# 03_-_Module_Sim.net
KiCad netlist of a schematic drawn in Altium Designer
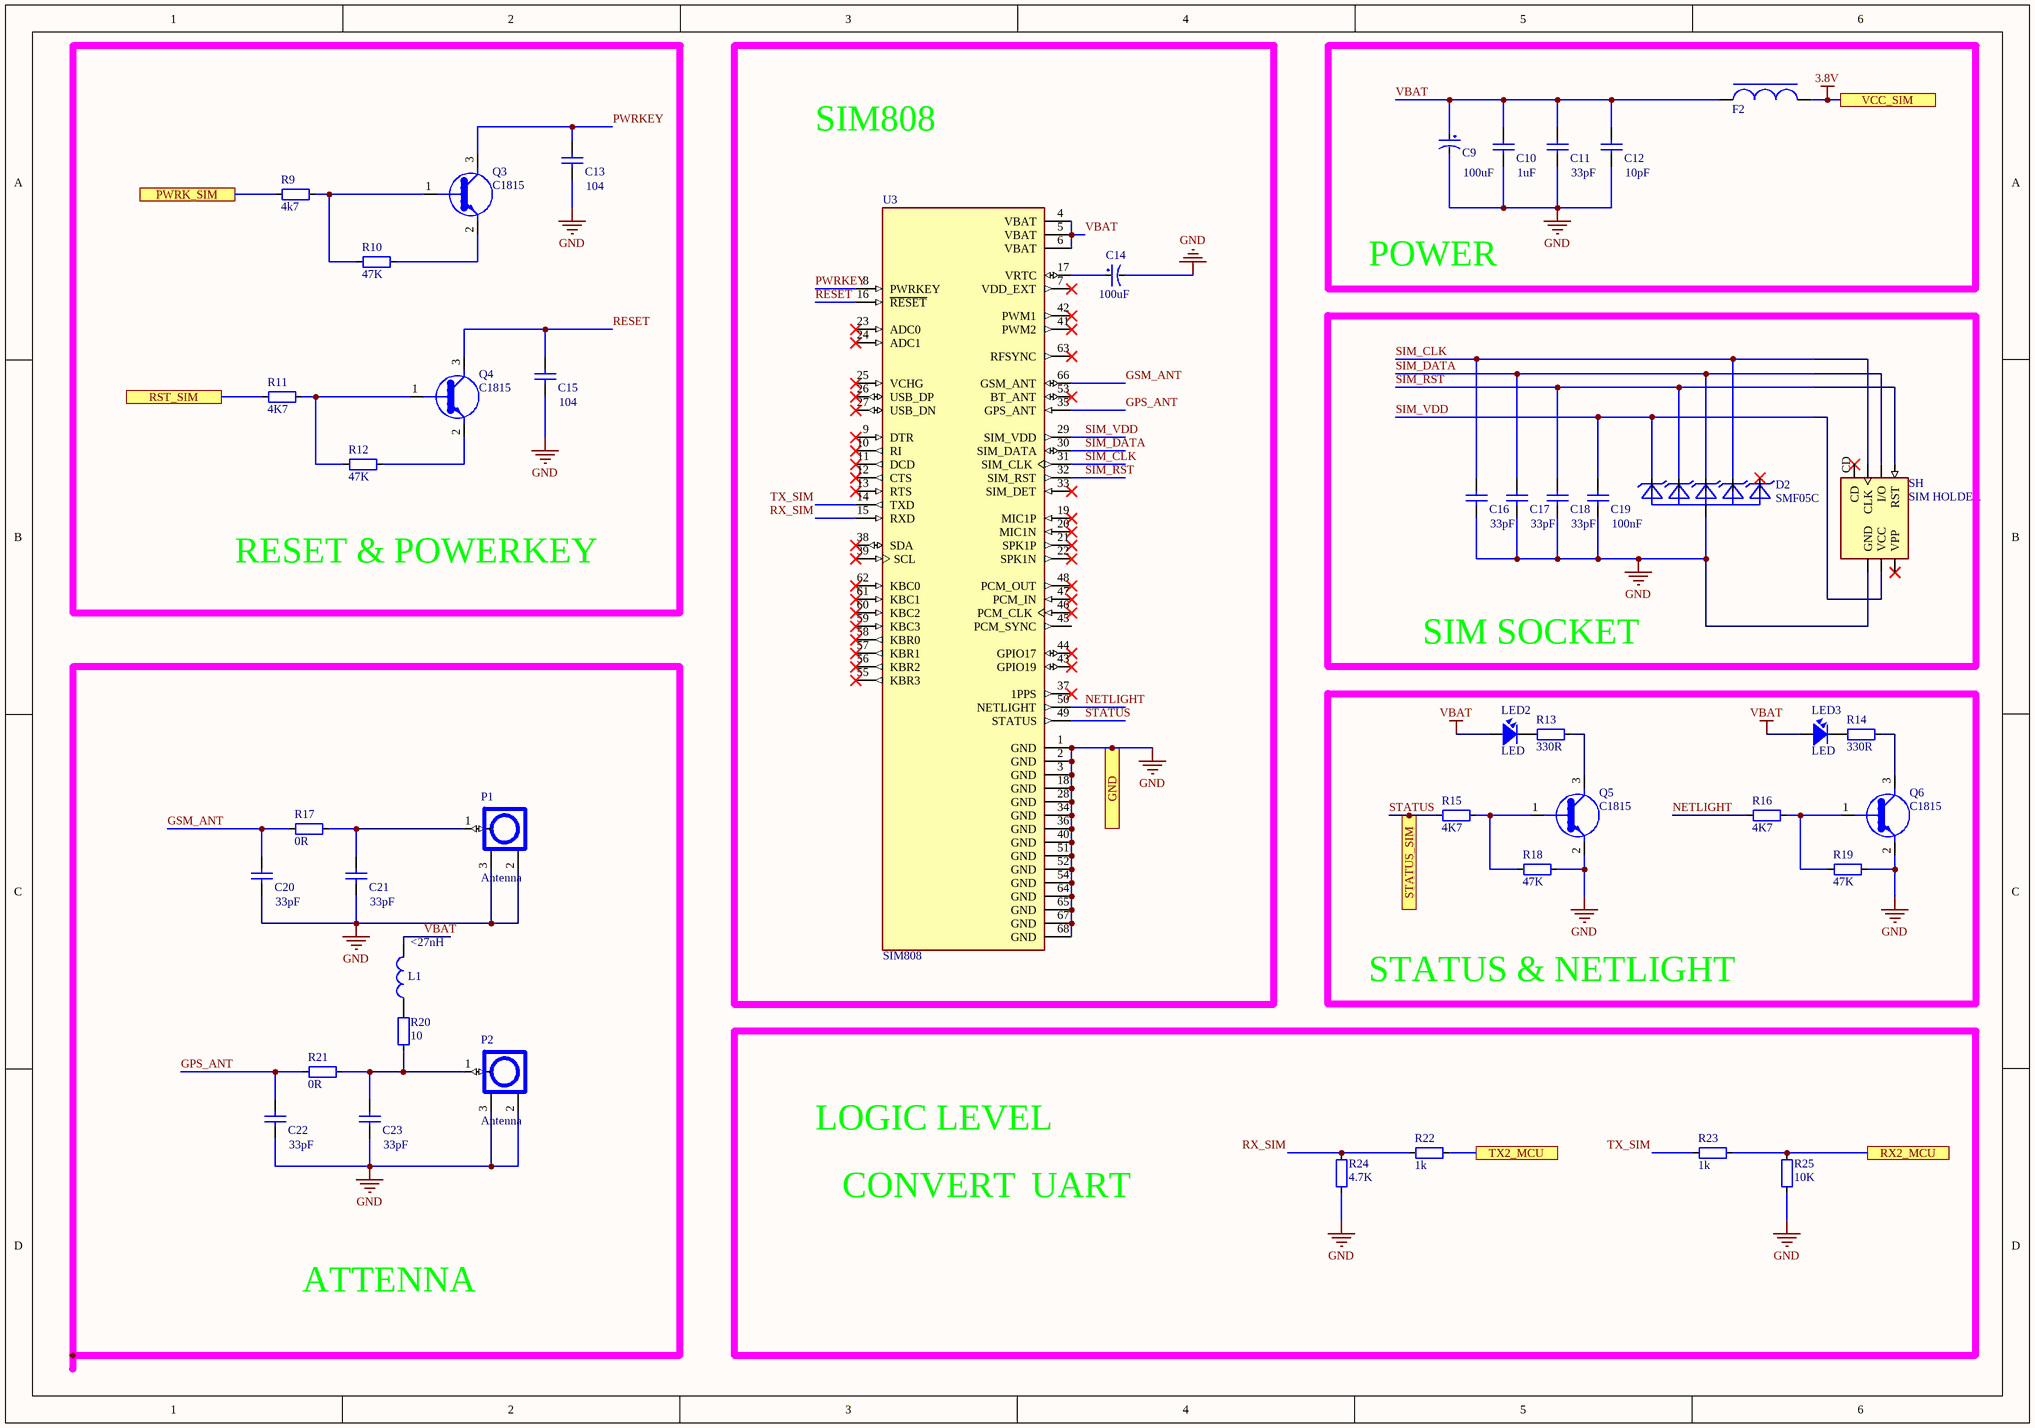
[diagram p0: [03] - Module Sim.SchDoc]

(export (version "E")
  (design (tool "Eeschema 10.0.6"))
  (components
    (comp (ref "C9")
      (value "100uF")
      (footprint "CAP-ALU-SMD-D")
      (description "Capacitor ALU SMD")
      (libsource (lib "HS_Lib") (part "Cap_ALU_Smd"))
    )
    (comp (ref "C10")
      (value "1uF")
      (footprint "CAP_0805")
      (description "Capacitor")
      (fields (field (name "PUBLISHER") "Altium Limited"))
      (libsource (lib "HS_Lib") (part "CapSMD"))
    )
    (comp (ref "C11")
      (value "33pF")
      (footprint "CAP_0805")
      (description "Capacitor")
      (fields (field (name "PUBLISHER") "Altium Limited"))
      (libsource (lib "HS_Lib") (part "CapSMD"))
    )
    (comp (ref "C12")
      (value "10pF")
      (footprint "CAP_0805")
      (description "Capacitor")
      (fields (field (name "PUBLISHER") "Altium Limited"))
      (libsource (lib "HS_Lib") (part "CapSMD"))
    )
    (comp (ref "C13")
      (value "104")
      (footprint "CAP_0805")
      (description "Capacitor")
      (fields (field (name "PUBLISHER") "Altium Limited"))
      (libsource (lib "HS_Lib") (part "CapSMD"))
    )
    (comp (ref "C14")
      (value "100uF")
      (footprint "CAP-ALU-SMD-D")
      (description "Capacitor ALU SMD")
      (libsource (lib "HS_Lib") (part "Cap_ALU_Smd"))
    )
    (comp (ref "C15")
      (value "104")
      (footprint "CAP_0805")
      (description "Capacitor")
      (fields (field (name "PUBLISHER") "Altium Limited"))
      (libsource (lib "HS_Lib") (part "CapSMD"))
    )
    (comp (ref "C16")
      (value "33pF")
      (footprint "CAP_0805")
      (description "Capacitor")
      (fields (field (name "PUBLISHER") "Altium Limited"))
      (libsource (lib "HS_Lib") (part "CapSMD"))
    )
    (comp (ref "C17")
      (value "33pF")
      (footprint "CAP_0805")
      (description "Capacitor")
      (fields (field (name "PUBLISHER") "Altium Limited"))
      (libsource (lib "HS_Lib") (part "CapSMD"))
    )
    (comp (ref "C18")
      (value "33pF")
      (footprint "CAP_0805")
      (description "Capacitor")
      (fields (field (name "PUBLISHER") "Altium Limited"))
      (libsource (lib "HS_Lib") (part "CapSMD"))
    )
    (comp (ref "C19")
      (value "100nF")
      (footprint "CAP_0805")
      (description "Capacitor")
      (fields (field (name "PUBLISHER") "Altium Limited"))
      (libsource (lib "HS_Lib") (part "CapSMD"))
    )
    (comp (ref "C20")
      (value "33pF")
      (footprint "CAP_0805")
      (description "Capacitor")
      (fields (field (name "PUBLISHER") "Altium Limited"))
      (libsource (lib "HS_Lib") (part "CapSMD"))
    )
    (comp (ref "C21")
      (value "33pF")
      (footprint "CAP_0805")
      (description "Capacitor")
      (fields (field (name "PUBLISHER") "Altium Limited"))
      (libsource (lib "HS_Lib") (part "CapSMD"))
    )
    (comp (ref "C22")
      (value "33pF")
      (footprint "CAP_0805")
      (description "Capacitor")
      (fields (field (name "PUBLISHER") "Altium Limited"))
      (libsource (lib "HS_Lib") (part "CapSMD"))
    )
    (comp (ref "C23")
      (value "33pF")
      (footprint "CAP_0805")
      (description "Capacitor")
      (fields (field (name "PUBLISHER") "Altium Limited"))
      (libsource (lib "HS_Lib") (part "CapSMD"))
    )
    (comp (ref "D2")
      (value "SMF05C")
      (footprint "SC70-6L")
      (description "12.5V Clamp 8A _8/20Âµs_ Ipp Tvs Diode Surface Mount SC-88/SC70-6/SOT-363")
      (fields (field (name "MF") "ON Semiconductor") (field (name "MANUFACTURER") "Semtech"))
      (libsource (lib "HS_Lib") (part "SMF05C"))
    )
    (comp (ref "F2")
      (value "Ferrite Bead")
      (footprint "Ferrite_0805")
      (fields
        (field (name "MANUFACTURER") "Murata")
        (field (name "MANUFACTURER PART NUMBER") "BLM21PG300SN1D")
        (field (name "TOLERANCE") "25%")
      )
      (libsource (lib "HS_Lib") (part "Ferrite Bead"))
    )
    (comp (ref "L1")
      (value "<27nH")
      (footprint "RTK_Rover_Lib:L-SMD-D-7.3x7.3")
      (libsource (lib "HS_Lib") (part "Inductor"))
    )
    (comp (ref "LED2")
      (value "LED")
      (footprint "LED-0805-Red")
      (description "LED Single colour Green and Red")
      (libsource (lib "RTK_Rover_Lib") (part "LED"))
    )
    (comp (ref "LED3")
      (value "LED")
      (footprint "LED-0805-Red")
      (description "LED Single colour Green and Red")
      (libsource (lib "RTK_Rover_Lib") (part "LED"))
    )
    (comp (ref "P1")
      (value "Antenna")
      (footprint "IPXS")
      (description "Antenna GSM GPS")
      (libsource (lib "HS_Lib") (part "IPXSx66"))
    )
    (comp (ref "P2")
      (value "Antenna")
      (footprint "IPXS")
      (description "Antenna GSM GPS")
      (libsource (lib "HS_Lib") (part "IPXSx66"))
    )
    (comp (ref "Q3")
      (value "C1815")
      (footprint "SOT23")
      (description "Bipolar _BJT_ Transistor NPN 25V 1.5A 100MHz 300mW Surface Mount SOT-23")
      (fields (field (name "MF") "Comchip Technology") (field (name "MP") "SS8050-G"))
      (libsource (lib "HS_Lib") (part "C1815"))
    )
    (comp (ref "Q4")
      (value "C1815")
      (footprint "SOT23")
      (description "Bipolar _BJT_ Transistor NPN 25V 1.5A 100MHz 300mW Surface Mount SOT-23")
      (fields (field (name "MF") "Comchip Technology") (field (name "MP") "SS8050-G"))
      (libsource (lib "HS_Lib") (part "C1815"))
    )
    (comp (ref "Q5")
      (value "C1815")
      (footprint "SOT23")
      (description "Bipolar _BJT_ Transistor NPN 25V 1.5A 100MHz 300mW Surface Mount SOT-23")
      (fields (field (name "MF") "Comchip Technology") (field (name "MP") "SS8050-G"))
      (libsource (lib "HS_Lib") (part "C1815"))
    )
    (comp (ref "Q6")
      (value "C1815")
      (footprint "SOT23")
      (description "Bipolar _BJT_ Transistor NPN 25V 1.5A 100MHz 300mW Surface Mount SOT-23")
      (fields (field (name "MF") "Comchip Technology") (field (name "MP") "SS8050-G"))
      (libsource (lib "HS_Lib") (part "C1815"))
    )
    (comp (ref "R9")
      (value "4k7")
      (footprint "RES-SMD-0805")
      (description "Resistor")
      (fields
        (field (name "MANUFACTURER") "Generic Components")
        (field (name "PUBLISHER") "Altium Hobart Technology Centre")
      )
      (libsource (lib "HS_Lib") (part "Resistor - SMD"))
    )
    (comp (ref "R10")
      (value "47K")
      (footprint "RES-SMD-0805")
      (description "Resistor")
      (fields
        (field (name "MANUFACTURER") "Generic Components")
        (field (name "PUBLISHER") "Altium Hobart Technology Centre")
      )
      (libsource (lib "HS_Lib") (part "Resistor - SMD"))
    )
    (comp (ref "R11")
      (value "4K7")
      (footprint "RES-SMD-0805")
      (description "Resistor")
      (fields
        (field (name "MANUFACTURER") "Generic Components")
        (field (name "PUBLISHER") "Altium Hobart Technology Centre")
      )
      (libsource (lib "HS_Lib") (part "Resistor - SMD"))
    )
    (comp (ref "R12")
      (value "47K")
      (footprint "RES-SMD-0805")
      (description "Resistor")
      (fields
        (field (name "MANUFACTURER") "Generic Components")
        (field (name "PUBLISHER") "Altium Hobart Technology Centre")
      )
      (libsource (lib "HS_Lib") (part "Resistor - SMD"))
    )
    (comp (ref "R13")
      (value "330R")
      (footprint "RES-SMD-0805")
      (description "Resistor")
      (fields
        (field (name "MANUFACTURER") "Generic Components")
        (field (name "PUBLISHER") "Altium Hobart Technology Centre")
      )
      (libsource (lib "RTK_Rover_Lib") (part "Resistor - SMD"))
    )
    (comp (ref "R14")
      (value "330R")
      (footprint "RES-SMD-0805")
      (description "Resistor")
      (fields
        (field (name "MANUFACTURER") "Generic Components")
        (field (name "PUBLISHER") "Altium Hobart Technology Centre")
      )
      (libsource (lib "RTK_Rover_Lib") (part "Resistor - SMD"))
    )
    (comp (ref "R15")
      (value "4K7")
      (footprint "RES-SMD-0805")
      (description "Resistor")
      (fields
        (field (name "MANUFACTURER") "Generic Components")
        (field (name "PUBLISHER") "Altium Hobart Technology Centre")
      )
      (libsource (lib "RTK_Rover_Lib") (part "Resistor - SMD"))
    )
    (comp (ref "R16")
      (value "4K7")
      (footprint "RES-SMD-0805")
      (description "Resistor")
      (fields
        (field (name "MANUFACTURER") "Generic Components")
        (field (name "PUBLISHER") "Altium Hobart Technology Centre")
      )
      (libsource (lib "RTK_Rover_Lib") (part "Resistor - SMD"))
    )
    (comp (ref "R17")
      (value "0R")
      (footprint "RES-SMD-0603")
      (description "Resistor")
      (fields
        (field (name "MANUFACTURER") "Generic Components")
        (field (name "PUBLISHER") "Altium Hobart Technology Centre")
      )
      (libsource (lib "My Library") (part "Resistor - SMD"))
    )
    (comp (ref "R18")
      (value "47K")
      (footprint "RES-SMD-0805")
      (description "Resistor")
      (fields
        (field (name "MANUFACTURER") "Generic Components")
        (field (name "PUBLISHER") "Altium Hobart Technology Centre")
      )
      (libsource (lib "RTK_Rover_Lib") (part "Resistor - SMD"))
    )
    (comp (ref "R19")
      (value "47K")
      (footprint "RES-SMD-0805")
      (description "Resistor")
      (fields
        (field (name "MANUFACTURER") "Generic Components")
        (field (name "PUBLISHER") "Altium Hobart Technology Centre")
      )
      (libsource (lib "RTK_Rover_Lib") (part "Resistor - SMD"))
    )
    (comp (ref "R20")
      (value "10")
      (footprint "RES-SMD-0603")
      (description "Resistor")
      (fields
        (field (name "MANUFACTURER") "Generic Components")
        (field (name "PUBLISHER") "Altium Hobart Technology Centre")
      )
      (libsource (lib "HS_Lib") (part "Resistor - SMD"))
    )
    (comp (ref "R21")
      (value "0R")
      (footprint "RES-SMD-0603")
      (description "Resistor")
      (fields
        (field (name "MANUFACTURER") "Generic Components")
        (field (name "PUBLISHER") "Altium Hobart Technology Centre")
      )
      (libsource (lib "My Library") (part "Resistor - SMD"))
    )
    (comp (ref "R22")
      (value "1k")
      (footprint "RES-SMD-0805")
      (description "Resistor")
      (fields
        (field (name "MANUFACTURER") "Generic Components")
        (field (name "PUBLISHER") "Altium Hobart Technology Centre")
      )
      (libsource (lib "HS_Lib") (part "Resistor - SMD"))
    )
    (comp (ref "R23")
      (value "1k")
      (footprint "RES-SMD-0805")
      (description "Resistor")
      (fields
        (field (name "MANUFACTURER") "Generic Components")
        (field (name "PUBLISHER") "Altium Hobart Technology Centre")
      )
      (libsource (lib "HS_Lib") (part "Resistor - SMD"))
    )
    (comp (ref "R24")
      (value "4.7K")
      (footprint "RES-SMD-0805")
      (description "Resistor")
      (fields
        (field (name "MANUFACTURER") "Generic Components")
        (field (name "PUBLISHER") "Altium Hobart Technology Centre")
      )
      (libsource (lib "HS_Lib") (part "Resistor - SMD"))
    )
    (comp (ref "R25")
      (value "10K")
      (footprint "RES-SMD-0805")
      (description "Resistor")
      (fields
        (field (name "MANUFACTURER") "Generic Components")
        (field (name "PUBLISHER") "Altium Hobart Technology Centre")
      )
      (libsource (lib "HS_Lib") (part "Resistor - SMD"))
    )
    (comp (ref "SH")
      (value "SIM HOLDER")
      (footprint "GCT_SIM7100-6-1-15-00-A_REVC")
      (description "7 _6 + 1_ Position Card Connector Micro SIM Surface Mount, Right Angle Gold")
      (fields (field (name "MP") "SIM7100-6-1-15-00-A") (field (name "MF") "Global Connector Technology"))
      (libsource (lib "HS_Lib") (part "SIM HOLDER"))
    )
    (comp (ref "U3")
      (value "SIM808")
      (footprint "XCVR_SIM808")
      (description "SIM808 GPS, GPRS/GSM RF Arduino Platform Evaluation Expansion Board")
      (fields (field (name "MF") "Adafruit Industries"))
      (libsource (lib "HS_Lib") (part "SIM808"))
    )
  )
  (nets
    (net (code "1") (name "/GPS_ANT") (class "Default")
      (node (ref "C22") (pin "2") (pinfunction "2_2") (pintype "passive"))
      (node (ref "R21") (pin "1") (pinfunction "1_1") (pintype "passive"))
      (node (ref "U3") (pin "35") (pinfunction "GPS_ANT_35") (pintype "input"))
    )
    (net (code "2") (name "/GSM_ANT") (class "Default")
      (node (ref "C20") (pin "2") (pinfunction "2_2") (pintype "passive"))
      (node (ref "R17") (pin "1") (pinfunction "1_1") (pintype "passive"))
      (node (ref "U3") (pin "66") (pinfunction "GSM_ANT_66") (pintype "bidirectional"))
    )
    (net (code "3") (name "/NETLIGHT") (class "Default")
      (node (ref "R16") (pin "1") (pinfunction "1_1") (pintype "passive"))
      (node (ref "U3") (pin "50") (pinfunction "NETLIGHT_50") (pintype "output"))
    )
    (net (code "4") (name "/PWRKEY") (class "Default")
      (node (ref "C13") (pin "2") (pinfunction "2_2") (pintype "passive"))
      (node (ref "Q3") (pin "3") (pinfunction "C_3") (pintype "power_in"))
      (node (ref "U3") (pin "8") (pinfunction "PWRKEY_8") (pintype "input"))
    )
    (net (code "5") (name "/PWRK_SIM") (class "Default")
      (node (ref "R9") (pin "1") (pinfunction "1_1") (pintype "passive"))
    )
    (net (code "6") (name "/RESET") (class "Default")
      (node (ref "C15") (pin "2") (pinfunction "2_2") (pintype "passive"))
      (node (ref "Q4") (pin "3") (pinfunction "C_3") (pintype "power_in"))
      (node (ref "U3") (pin "16") (pinfunction "~{RESET}_16") (pintype "input"))
    )
    (net (code "7") (name "/RST_SIM") (class "Default")
      (node (ref "R11") (pin "1") (pinfunction "1_1") (pintype "passive"))
    )
    (net (code "8") (name "/RX2_MCU") (class "Default")
      (node (ref "R23") (pin "1") (pinfunction "1_1") (pintype "passive"))
      (node (ref "R25") (pin "1") (pinfunction "1_1") (pintype "passive"))
    )
    (net (code "9") (name "/RX_SIM") (class "Default")
      (node (ref "R22") (pin "2") (pinfunction "2_2") (pintype "passive"))
      (node (ref "R24") (pin "2") (pinfunction "2_2") (pintype "passive"))
      (node (ref "U3") (pin "15") (pinfunction "RXD_15") (pintype "input"))
    )
    (net (code "10") (name "/SIM_CLK") (class "Default")
      (node (ref "C16") (pin "2") (pinfunction "2_2") (pintype "passive"))
      (node (ref "D2") (pin "5") (pinfunction "C4_5") (pintype "passive"))
      (node (ref "SH") (pin "C3") (pinfunction "CLK_C3") (pintype "bidirectional"))
      (node (ref "U3") (pin "31") (pinfunction "SIM_CLK_31") (pintype "output"))
    )
    (net (code "11") (name "/SIM_DATA") (class "Default")
      (node (ref "C17") (pin "2") (pinfunction "2_2") (pintype "passive"))
      (node (ref "D2") (pin "4") (pinfunction "C3_4") (pintype "passive"))
      (node (ref "SH") (pin "C7") (pinfunction "I/O_C7") (pintype "bidirectional"))
      (node (ref "U3") (pin "30") (pinfunction "SIM_DATA_30") (pintype "bidirectional"))
    )
    (net (code "12") (name "/SIM_RST") (class "Default")
      (node (ref "C18") (pin "2") (pinfunction "2_2") (pintype "passive"))
      (node (ref "D2") (pin "3") (pinfunction "C2_3") (pintype "passive"))
      (node (ref "SH") (pin "C2") (pinfunction "RST_C2") (pintype "input"))
      (node (ref "U3") (pin "32") (pinfunction "SIM_RST_32") (pintype "output"))
    )
    (net (code "13") (name "/SIM_VDD") (class "Default")
      (node (ref "C19") (pin "2") (pinfunction "2_2") (pintype "passive"))
      (node (ref "D2") (pin "1") (pinfunction "C1_1") (pintype "passive"))
      (node (ref "SH") (pin "C1") (pinfunction "VCC_C1") (pintype "power_in"))
      (node (ref "U3") (pin "29") (pinfunction "SIM_VDD_29") (pintype "output"))
    )
    (net (code "14") (name "/STATUS") (class "Default")
      (node (ref "R15") (pin "2") (pinfunction "2_2") (pintype "passive"))
      (node (ref "U3") (pin "49") (pinfunction "STATUS_49") (pintype "output"))
    )
    (net (code "15") (name "/TX2_MCU") (class "Default")
      (node (ref "R22") (pin "1") (pinfunction "1_1") (pintype "passive"))
    )
    (net (code "16") (name "/TX_SIM") (class "Default")
      (node (ref "R23") (pin "2") (pinfunction "2_2") (pintype "passive"))
      (node (ref "U3") (pin "14") (pinfunction "TXD_14") (pintype "output"))
    )
    (net (code "17") (name "3.8V") (class "Default")
      (node (ref "F2") (pin "2") (pinfunction "2_2") (pintype "power_in"))
    )
    (net (code "18") (name "GND") (class "Default")
      (node (ref "C10") (pin "1") (pinfunction "1_1") (pintype "passive"))
      (node (ref "C11") (pin "1") (pinfunction "1_1") (pintype "passive"))
      (node (ref "C12") (pin "1") (pinfunction "1_1") (pintype "passive"))
      (node (ref "C13") (pin "1") (pinfunction "1_1") (pintype "passive"))
      (node (ref "C14") (pin "2") (pinfunction "2_2") (pintype "passive"))
      (node (ref "C15") (pin "1") (pinfunction "1_1") (pintype "passive"))
      (node (ref "C16") (pin "1") (pinfunction "1_1") (pintype "passive"))
      (node (ref "C17") (pin "1") (pinfunction "1_1") (pintype "passive"))
      (node (ref "C18") (pin "1") (pinfunction "1_1") (pintype "passive"))
      (node (ref "C19") (pin "1") (pinfunction "1_1") (pintype "passive"))
      (node (ref "C20") (pin "1") (pinfunction "1_1") (pintype "passive"))
      (node (ref "C21") (pin "1") (pinfunction "1_1") (pintype "passive"))
      (node (ref "C22") (pin "1") (pinfunction "1_1") (pintype "passive"))
      (node (ref "C23") (pin "1") (pinfunction "1_1") (pintype "passive"))
      (node (ref "C9") (pin "2") (pinfunction "2_2") (pintype "passive"))
      (node (ref "D2") (pin "2") (pinfunction "A_2") (pintype "passive"))
      (node (ref "P1") (pin "2") (pintype "passive"))
      (node (ref "P1") (pin "3") (pintype "passive"))
      (node (ref "P2") (pin "2") (pintype "passive"))
      (node (ref "P2") (pin "3") (pintype "passive"))
      (node (ref "Q5") (pin "2") (pinfunction "E_2") (pintype "power_in"))
      (node (ref "Q6") (pin "2") (pinfunction "E_2") (pintype "power_in"))
      (node (ref "R18") (pin "2") (pinfunction "2_2") (pintype "passive"))
      (node (ref "R19") (pin "2") (pinfunction "2_2") (pintype "passive"))
      (node (ref "R24") (pin "1") (pinfunction "1_1") (pintype "passive"))
      (node (ref "R25") (pin "2") (pinfunction "2_2") (pintype "passive"))
      (node (ref "SH") (pin "C5") (pinfunction "GND_C5") (pintype "power_in"))
      (node (ref "U3") (pin "1") (pinfunction "GND_1") (pintype "power_in"))
      (node (ref "U3") (pin "18") (pinfunction "GND_18") (pintype "power_in"))
      (node (ref "U3") (pin "2") (pinfunction "GND_2") (pintype "power_in"))
      (node (ref "U3") (pin "28") (pinfunction "GND_28") (pintype "power_in"))
      (node (ref "U3") (pin "3") (pinfunction "GND_3") (pintype "power_in"))
      (node (ref "U3") (pin "34") (pinfunction "GND_34") (pintype "power_in"))
      (node (ref "U3") (pin "36") (pinfunction "GND_36") (pintype "power_in"))
      (node (ref "U3") (pin "40") (pinfunction "GND_40") (pintype "power_in"))
      (node (ref "U3") (pin "51") (pinfunction "GND_51") (pintype "power_in"))
      (node (ref "U3") (pin "52") (pinfunction "GND_52") (pintype "power_in"))
      (node (ref "U3") (pin "54") (pinfunction "GND_54") (pintype "power_in"))
      (node (ref "U3") (pin "64") (pinfunction "GND_64") (pintype "power_in"))
      (node (ref "U3") (pin "65") (pinfunction "GND_65") (pintype "power_in"))
      (node (ref "U3") (pin "67") (pinfunction "GND_67") (pintype "power_in"))
      (node (ref "U3") (pin "68") (pinfunction "GND_68") (pintype "power_in"))
    )
    (net (code "19") (name "Net-(C21-Pad2)") (class "Default")
      (node (ref "C21") (pin "2") (pinfunction "2_2") (pintype "passive"))
      (node (ref "P1") (pin "1") (pintype "bidirectional"))
      (node (ref "R17") (pin "2") (pinfunction "2_2") (pintype "passive"))
    )
    (net (code "20") (name "Net-(C23-Pad2)") (class "Default")
      (node (ref "C23") (pin "2") (pinfunction "2_2") (pintype "passive"))
      (node (ref "P2") (pin "1") (pintype "bidirectional"))
      (node (ref "R20") (pin "1") (pinfunction "1_1") (pintype "passive"))
      (node (ref "R21") (pin "2") (pinfunction "2_2") (pintype "passive"))
    )
    (net (code "21") (name "Net-(L1-Pad1)") (class "Default")
      (node (ref "L1") (pin "1") (pinfunction "1_1") (pintype "passive"))
      (node (ref "R20") (pin "2") (pinfunction "2_2") (pintype "passive"))
    )
    (net (code "22") (name "Net-(LED2-Pad2)") (class "Default")
      (node (ref "LED2") (pin "2") (pinfunction "2_2") (pintype "passive"))
      (node (ref "R13") (pin "1") (pinfunction "1_1") (pintype "passive"))
    )
    (net (code "23") (name "Net-(LED3-Pad2)") (class "Default")
      (node (ref "LED3") (pin "2") (pinfunction "2_2") (pintype "passive"))
      (node (ref "R14") (pin "1") (pinfunction "1_1") (pintype "passive"))
    )
    (net (code "24") (name "Net-(Q3-B)") (class "Default")
      (node (ref "Q3") (pin "1") (pinfunction "B_1") (pintype "power_in"))
      (node (ref "R10") (pin "1") (pinfunction "1_1") (pintype "passive"))
      (node (ref "R9") (pin "2") (pinfunction "2_2") (pintype "passive"))
    )
    (net (code "25") (name "Net-(Q3-E)") (class "Default")
      (node (ref "Q3") (pin "2") (pinfunction "E_2") (pintype "power_in"))
      (node (ref "R10") (pin "2") (pinfunction "2_2") (pintype "passive"))
    )
    (net (code "26") (name "Net-(Q4-B)") (class "Default")
      (node (ref "Q4") (pin "1") (pinfunction "B_1") (pintype "power_in"))
      (node (ref "R11") (pin "2") (pinfunction "2_2") (pintype "passive"))
      (node (ref "R12") (pin "1") (pinfunction "1_1") (pintype "passive"))
    )
    (net (code "27") (name "Net-(Q4-E)") (class "Default")
      (node (ref "Q4") (pin "2") (pinfunction "E_2") (pintype "power_in"))
      (node (ref "R12") (pin "2") (pinfunction "2_2") (pintype "passive"))
    )
    (net (code "28") (name "Net-(Q5-B)") (class "Default")
      (node (ref "Q5") (pin "1") (pinfunction "B_1") (pintype "power_in"))
      (node (ref "R15") (pin "1") (pinfunction "1_1") (pintype "passive"))
      (node (ref "R18") (pin "1") (pinfunction "1_1") (pintype "passive"))
    )
    (net (code "29") (name "Net-(Q5-C)") (class "Default")
      (node (ref "Q5") (pin "3") (pinfunction "C_3") (pintype "power_in"))
      (node (ref "R13") (pin "2") (pinfunction "2_2") (pintype "passive"))
    )
    (net (code "30") (name "Net-(Q6-B)") (class "Default")
      (node (ref "Q6") (pin "1") (pinfunction "B_1") (pintype "power_in"))
      (node (ref "R16") (pin "2") (pinfunction "2_2") (pintype "passive"))
      (node (ref "R19") (pin "1") (pinfunction "1_1") (pintype "passive"))
    )
    (net (code "31") (name "Net-(Q6-C)") (class "Default")
      (node (ref "Q6") (pin "3") (pinfunction "C_3") (pintype "power_in"))
      (node (ref "R14") (pin "2") (pinfunction "2_2") (pintype "passive"))
    )
    (net (code "32") (name "Net-(U3-VRTC)") (class "Default")
      (node (ref "C14") (pin "1") (pinfunction "1_1") (pintype "passive"))
      (node (ref "U3") (pin "17") (pinfunction "VRTC_17") (pintype "bidirectional"))
    )
    (net (code "33") (name "VBAT") (class "Default")
      (node (ref "C10") (pin "2") (pinfunction "2_2") (pintype "passive"))
      (node (ref "C11") (pin "2") (pinfunction "2_2") (pintype "passive"))
      (node (ref "C12") (pin "2") (pinfunction "2_2") (pintype "passive"))
      (node (ref "C9") (pin "1") (pinfunction "1_1") (pintype "passive"))
      (node (ref "F2") (pin "1") (pinfunction "1_1") (pintype "power_in"))
      (node (ref "L1") (pin "2") (pinfunction "2_2") (pintype "passive"))
      (node (ref "LED2") (pin "1") (pinfunction "1_1") (pintype "passive"))
      (node (ref "LED3") (pin "1") (pinfunction "1_1") (pintype "passive"))
      (node (ref "U3") (pin "4") (pinfunction "VBAT_4") (pintype "power_in"))
      (node (ref "U3") (pin "5") (pinfunction "VBAT_5") (pintype "power_in"))
      (node (ref "U3") (pin "6") (pinfunction "VBAT_6") (pintype "power_in"))
    )
    (net (code "34") (name "unconnected-(D2-C5-Pad6)") (class "Default")
      (node (ref "D2") (pin "6") (pinfunction "C5_6") (pintype "passive+no_connect"))
    )
    (net (code "35") (name "unconnected-(SH-PadCD)") (class "Default")
      (node (ref "SH") (pin "CD") (pinfunction "CD_CD") (pintype "passive+no_connect"))
    )
    (net (code "36") (name "unconnected-(SH-VPP-PadC6)") (class "Default")
      (node (ref "SH") (pin "C6") (pinfunction "VPP_C6") (pintype "power_in+no_connect"))
    )
    (net (code "37") (name "unconnected-(U3-1PPS-Pad37)") (class "Default")
      (node (ref "U3") (pin "37") (pinfunction "1PPS_37") (pintype "output+no_connect"))
    )
    (net (code "38") (name "unconnected-(U3-ADC0-Pad23)") (class "Default")
      (node (ref "U3") (pin "23") (pinfunction "ADC0_23") (pintype "input+no_connect"))
    )
    (net (code "39") (name "unconnected-(U3-ADC1-Pad24)") (class "Default")
      (node (ref "U3") (pin "24") (pinfunction "ADC1_24") (pintype "input+no_connect"))
    )
    (net (code "40") (name "unconnected-(U3-BT_ANT-Pad53)") (class "Default")
      (node (ref "U3") (pin "53") (pinfunction "BT_ANT_53") (pintype "bidirectional+no_connect"))
    )
    (net (code "41") (name "unconnected-(U3-CTS-Pad12)") (class "Default")
      (node (ref "U3") (pin "12") (pinfunction "CTS_12") (pintype "output+no_connect"))
    )
    (net (code "42") (name "unconnected-(U3-DCD-Pad11)") (class "Default")
      (node (ref "U3") (pin "11") (pinfunction "DCD_11") (pintype "output+no_connect"))
    )
    (net (code "43") (name "unconnected-(U3-DTR-Pad9)") (class "Default")
      (node (ref "U3") (pin "9") (pinfunction "DTR_9") (pintype "input+no_connect"))
    )
    (net (code "44") (name "unconnected-(U3-GPIO17-Pad44)") (class "Default")
      (node (ref "U3") (pin "44") (pinfunction "GPIO17_44") (pintype "bidirectional+no_connect"))
    )
    (net (code "45") (name "unconnected-(U3-GPIO19-Pad43)") (class "Default")
      (node (ref "U3") (pin "43") (pinfunction "GPIO19_43") (pintype "bidirectional+no_connect"))
    )
    (net (code "46") (name "unconnected-(U3-KBC0-Pad62)") (class "Default")
      (node (ref "U3") (pin "62") (pinfunction "KBC0_62") (pintype "input+no_connect"))
    )
    (net (code "47") (name "unconnected-(U3-KBC1-Pad61)") (class "Default")
      (node (ref "U3") (pin "61") (pinfunction "KBC1_61") (pintype "input+no_connect"))
    )
    (net (code "48") (name "unconnected-(U3-KBC2-Pad60)") (class "Default")
      (node (ref "U3") (pin "60") (pinfunction "KBC2_60") (pintype "input+no_connect"))
    )
    (net (code "49") (name "unconnected-(U3-KBC3-Pad59)") (class "Default")
      (node (ref "U3") (pin "59") (pinfunction "KBC3_59") (pintype "input+no_connect"))
    )
    (net (code "50") (name "unconnected-(U3-KBR0-Pad58)") (class "Default")
      (node (ref "U3") (pin "58") (pinfunction "KBR0_58") (pintype "output+no_connect"))
    )
    (net (code "51") (name "unconnected-(U3-KBR1-Pad57)") (class "Default")
      (node (ref "U3") (pin "57") (pinfunction "KBR1_57") (pintype "output+no_connect"))
    )
    (net (code "52") (name "unconnected-(U3-KBR2-Pad56)") (class "Default")
      (node (ref "U3") (pin "56") (pinfunction "KBR2_56") (pintype "output+no_connect"))
    )
    (net (code "53") (name "unconnected-(U3-KBR3-Pad55)") (class "Default")
      (node (ref "U3") (pin "55") (pinfunction "KBR3_55") (pintype "output+no_connect"))
    )
    (net (code "54") (name "unconnected-(U3-MIC1N-Pad20)") (class "Default")
      (node (ref "U3") (pin "20") (pinfunction "MIC1N_20") (pintype "input+no_connect"))
    )
    (net (code "55") (name "unconnected-(U3-MIC1P-Pad19)") (class "Default")
      (node (ref "U3") (pin "19") (pinfunction "MIC1P_19") (pintype "input+no_connect"))
    )
    (net (code "56") (name "unconnected-(U3-PCM_CLK-Pad46)") (class "Default")
      (node (ref "U3") (pin "46") (pinfunction "PCM_CLK_46") (pintype "input+no_connect"))
    )
    (net (code "57") (name "unconnected-(U3-PCM_IN-Pad47)") (class "Default")
      (node (ref "U3") (pin "47") (pinfunction "PCM_IN_47") (pintype "input+no_connect"))
    )
    (net (code "58") (name "unconnected-(U3-PCM_OUT-Pad48)") (class "Default")
      (node (ref "U3") (pin "48") (pinfunction "PCM_OUT_48") (pintype "output+no_connect"))
    )
    (net (code "59") (name "unconnected-(U3-PCM_SYNC-Pad45)") (class "Default")
      (node (ref "U3") (pin "45") (pinfunction "PCM_SYNC_45") (pintype "output"))
    )
    (net (code "60") (name "unconnected-(U3-PWM1-Pad42)") (class "Default")
      (node (ref "U3") (pin "42") (pinfunction "PWM1_42") (pintype "output+no_connect"))
    )
    (net (code "61") (name "unconnected-(U3-PWM2-Pad41)") (class "Default")
      (node (ref "U3") (pin "41") (pinfunction "PWM2_41") (pintype "output+no_connect"))
    )
    (net (code "62") (name "unconnected-(U3-RFSYNC-Pad63)") (class "Default")
      (node (ref "U3") (pin "63") (pinfunction "RFSYNC_63") (pintype "output+no_connect"))
    )
    (net (code "63") (name "unconnected-(U3-RI-Pad10)") (class "Default")
      (node (ref "U3") (pin "10") (pinfunction "RI_10") (pintype "output+no_connect"))
    )
    (net (code "64") (name "unconnected-(U3-RTS-Pad13)") (class "Default")
      (node (ref "U3") (pin "13") (pinfunction "RTS_13") (pintype "input+no_connect"))
    )
    (net (code "65") (name "unconnected-(U3-SCL-Pad39)") (class "Default")
      (node (ref "U3") (pin "39") (pinfunction "SCL_39") (pintype "input+no_connect"))
    )
    (net (code "66") (name "unconnected-(U3-SDA-Pad38)") (class "Default")
      (node (ref "U3") (pin "38") (pinfunction "SDA_38") (pintype "bidirectional+no_connect"))
    )
    (net (code "67") (name "unconnected-(U3-SIM_DET-Pad33)") (class "Default")
      (node (ref "U3") (pin "33") (pinfunction "SIM_DET_33") (pintype "input+no_connect"))
    )
    (net (code "68") (name "unconnected-(U3-SPK1N-Pad22)") (class "Default")
      (node (ref "U3") (pin "22") (pinfunction "SPK1N_22") (pintype "output+no_connect"))
    )
    (net (code "69") (name "unconnected-(U3-SPK1P-Pad21)") (class "Default")
      (node (ref "U3") (pin "21") (pinfunction "SPK1P_21") (pintype "output+no_connect"))
    )
    (net (code "70") (name "unconnected-(U3-USB_DN-Pad27)") (class "Default")
      (node (ref "U3") (pin "27") (pinfunction "USB_DN_27") (pintype "bidirectional+no_connect"))
    )
    (net (code "71") (name "unconnected-(U3-USB_DP-Pad26)") (class "Default")
      (node (ref "U3") (pin "26") (pinfunction "USB_DP_26") (pintype "bidirectional+no_connect"))
    )
    (net (code "72") (name "unconnected-(U3-VCHG-Pad25)") (class "Default")
      (node (ref "U3") (pin "25") (pinfunction "VCHG_25") (pintype "input+no_connect"))
    )
    (net (code "73") (name "unconnected-(U3-VDD_EXT-Pad7)") (class "Default")
      (node (ref "U3") (pin "7") (pinfunction "VDD_EXT_7") (pintype "output+no_connect"))
    )
  )
)
